# snes_exp_bridge.net
KiCad netlist of a schematic drawn in Altium Designer
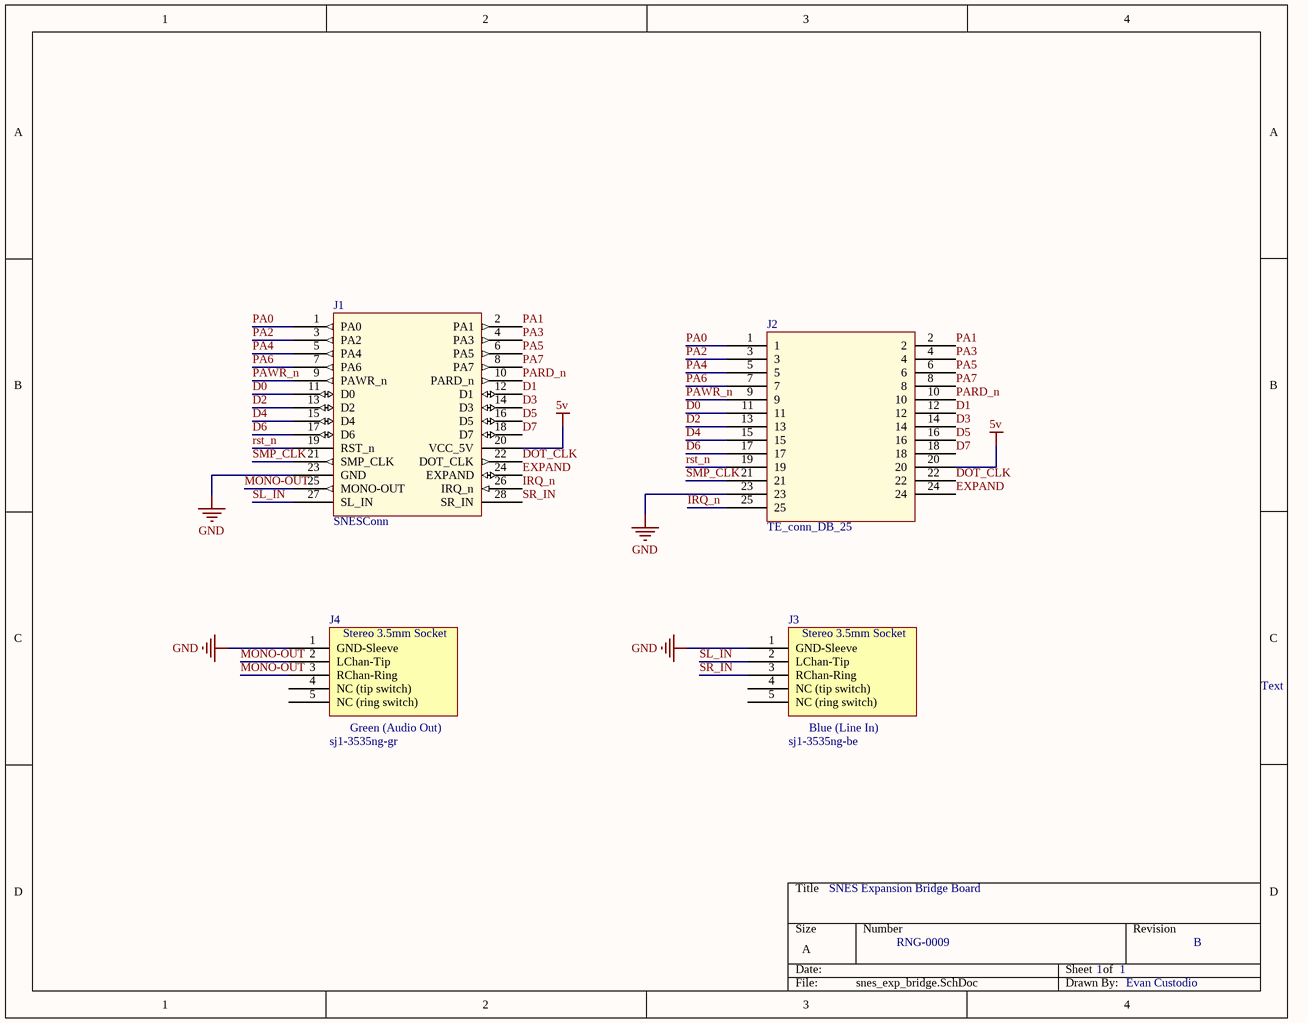
[diagram p0: snes_exp_bridge.SchDoc]

(export (version "E")
  (design (tool "Eeschema 10.0.6"))
  (components
    (comp (ref "J1")
      (value "SNESConn")
      (footprint "SNES-MEC2-CONN")
      (libsource (lib "snes_hook_parts") (part "SNESConn"))
    )
    (comp (ref "J2")
      (value "TE_conn_DB_25")
      (footprint "DB-25_RA_FSCK")
      (libsource (lib "snes_exp_bridge_parts") (part "TE_conn_DB_25"))
    )
    (comp (ref "J3")
      (value "sj1-3535ng-be")
      (footprint "SJ1-3535NG-BE")
      (libsource (lib "snes_exp_bridge_parts") (part "sj1-3535ng-be"))
    )
    (comp (ref "J4")
      (value "sj1-3535ng-gr")
      (footprint "SJ1-3535NG-GR")
      (libsource (lib "snes_exp_bridge_parts") (part "sj1-3535ng-gr"))
    )
  )
  (nets
    (net (code "1") (name "/D0") (class "Default")
      (node (ref "J1") (pin "11") (pinfunction "D0_11") (pintype "bidirectional"))
      (node (ref "J2") (pin "11") (pinfunction "11_11") (pintype "passive"))
    )
    (net (code "2") (name "/D1") (class "Default")
      (node (ref "J1") (pin "12") (pinfunction "D1_12") (pintype "bidirectional"))
      (node (ref "J2") (pin "12") (pinfunction "12_12") (pintype "passive"))
    )
    (net (code "3") (name "/D2") (class "Default")
      (node (ref "J1") (pin "13") (pinfunction "D2_13") (pintype "bidirectional"))
      (node (ref "J2") (pin "13") (pinfunction "13_13") (pintype "passive"))
    )
    (net (code "4") (name "/D3") (class "Default")
      (node (ref "J1") (pin "14") (pinfunction "D3_14") (pintype "bidirectional"))
      (node (ref "J2") (pin "14") (pinfunction "14_14") (pintype "passive"))
    )
    (net (code "5") (name "/D4") (class "Default")
      (node (ref "J1") (pin "15") (pinfunction "D4_15") (pintype "bidirectional"))
      (node (ref "J2") (pin "15") (pinfunction "15_15") (pintype "passive"))
    )
    (net (code "6") (name "/D5") (class "Default")
      (node (ref "J1") (pin "16") (pinfunction "D5_16") (pintype "bidirectional"))
      (node (ref "J2") (pin "16") (pinfunction "16_16") (pintype "passive"))
    )
    (net (code "7") (name "/D6") (class "Default")
      (node (ref "J1") (pin "17") (pinfunction "D6_17") (pintype "bidirectional"))
      (node (ref "J2") (pin "17") (pinfunction "17_17") (pintype "passive"))
    )
    (net (code "8") (name "/D7") (class "Default")
      (node (ref "J1") (pin "18") (pinfunction "D7_18") (pintype "bidirectional"))
      (node (ref "J2") (pin "18") (pinfunction "18_18") (pintype "passive"))
    )
    (net (code "9") (name "/DOT_CLK") (class "Default")
      (node (ref "J1") (pin "22") (pinfunction "DOT_CLK_22") (pintype "output"))
      (node (ref "J2") (pin "22") (pinfunction "22_22") (pintype "passive"))
    )
    (net (code "10") (name "/EXPAND") (class "Default")
      (node (ref "J1") (pin "24") (pinfunction "EXPAND_24") (pintype "bidirectional"))
      (node (ref "J2") (pin "24") (pinfunction "24_24") (pintype "passive"))
    )
    (net (code "11") (name "/IRQ_n") (class "Default")
      (node (ref "J1") (pin "26") (pinfunction "IRQ_n_26") (pintype "input"))
      (node (ref "J2") (pin "25") (pinfunction "25_25") (pintype "passive"))
    )
    (net (code "12") (name "/MONO-OUT") (class "Default")
      (node (ref "J1") (pin "25") (pinfunction "MONO-OUT_25") (pintype "output"))
      (node (ref "J4") (pin "2") (pinfunction "LChan-Tip_2") (pintype "passive"))
      (node (ref "J4") (pin "3") (pinfunction "RChan-Ring_3") (pintype "passive"))
    )
    (net (code "13") (name "/PA0") (class "Default")
      (node (ref "J1") (pin "1") (pinfunction "PA0_1") (pintype "output"))
      (node (ref "J2") (pin "1") (pinfunction "1_1") (pintype "passive"))
    )
    (net (code "14") (name "/PA1") (class "Default")
      (node (ref "J1") (pin "2") (pinfunction "PA1_2") (pintype "output"))
      (node (ref "J2") (pin "2") (pinfunction "2_2") (pintype "passive"))
    )
    (net (code "15") (name "/PA2") (class "Default")
      (node (ref "J1") (pin "3") (pinfunction "PA2_3") (pintype "output"))
      (node (ref "J2") (pin "3") (pinfunction "3_3") (pintype "passive"))
    )
    (net (code "16") (name "/PA3") (class "Default")
      (node (ref "J1") (pin "4") (pinfunction "PA3_4") (pintype "output"))
      (node (ref "J2") (pin "4") (pinfunction "4_4") (pintype "passive"))
    )
    (net (code "17") (name "/PA4") (class "Default")
      (node (ref "J1") (pin "5") (pinfunction "PA4_5") (pintype "output"))
      (node (ref "J2") (pin "5") (pinfunction "5_5") (pintype "passive"))
    )
    (net (code "18") (name "/PA5") (class "Default")
      (node (ref "J1") (pin "6") (pinfunction "PA5_6") (pintype "output"))
      (node (ref "J2") (pin "6") (pinfunction "6_6") (pintype "passive"))
    )
    (net (code "19") (name "/PA6") (class "Default")
      (node (ref "J1") (pin "7") (pinfunction "PA6_7") (pintype "output"))
      (node (ref "J2") (pin "7") (pinfunction "7_7") (pintype "passive"))
    )
    (net (code "20") (name "/PA7") (class "Default")
      (node (ref "J1") (pin "8") (pinfunction "PA7_8") (pintype "output"))
      (node (ref "J2") (pin "8") (pinfunction "8_8") (pintype "passive"))
    )
    (net (code "21") (name "/PARD_n") (class "Default")
      (node (ref "J1") (pin "10") (pinfunction "PARD_n_10") (pintype "output"))
      (node (ref "J2") (pin "10") (pinfunction "10_10") (pintype "passive"))
    )
    (net (code "22") (name "/PAWR_n") (class "Default")
      (node (ref "J1") (pin "9") (pinfunction "PAWR_n_9") (pintype "output"))
      (node (ref "J2") (pin "9") (pinfunction "9_9") (pintype "passive"))
    )
    (net (code "23") (name "/SL_IN") (class "Default")
      (node (ref "J1") (pin "27") (pinfunction "SL_IN_27") (pintype "passive"))
      (node (ref "J3") (pin "2") (pinfunction "LChan-Tip_2") (pintype "passive"))
    )
    (net (code "24") (name "/SMP_CLK") (class "Default")
      (node (ref "J1") (pin "21") (pinfunction "SMP_CLK_21") (pintype "output"))
      (node (ref "J2") (pin "21") (pinfunction "21_21") (pintype "passive"))
    )
    (net (code "25") (name "/SR_IN") (class "Default")
      (node (ref "J1") (pin "28") (pinfunction "SR_IN_28") (pintype "passive"))
      (node (ref "J3") (pin "3") (pinfunction "RChan-Ring_3") (pintype "passive"))
    )
    (net (code "26") (name "/rst_n") (class "Default")
      (node (ref "J1") (pin "19") (pinfunction "RST_n_19") (pintype "passive"))
      (node (ref "J2") (pin "19") (pinfunction "19_19") (pintype "passive"))
    )
    (net (code "27") (name "5v") (class "Default")
      (node (ref "J1") (pin "20") (pinfunction "VCC_5V_20") (pintype "passive"))
      (node (ref "J2") (pin "20") (pinfunction "20_20") (pintype "passive"))
    )
    (net (code "28") (name "GND") (class "Default")
      (node (ref "J1") (pin "23") (pinfunction "GND_23") (pintype "passive"))
      (node (ref "J2") (pin "23") (pinfunction "23_23") (pintype "passive"))
      (node (ref "J3") (pin "1") (pinfunction "GND-Sleeve_1") (pintype "passive"))
      (node (ref "J4") (pin "1") (pinfunction "GND-Sleeve_1") (pintype "passive"))
    )
    (net (code "29") (name "unconnected-(J3-NC_(ring_switch)-Pad5)") (class "Default")
      (node (ref "J3") (pin "5") (pinfunction "NC_(ring_switch)_5") (pintype "passive"))
    )
    (net (code "30") (name "unconnected-(J3-NC_(tip_switch)-Pad4)") (class "Default")
      (node (ref "J3") (pin "4") (pinfunction "NC_(tip_switch)_4") (pintype "passive"))
    )
    (net (code "31") (name "unconnected-(J4-NC_(ring_switch)-Pad5)") (class "Default")
      (node (ref "J4") (pin "5") (pinfunction "NC_(ring_switch)_5") (pintype "passive"))
    )
    (net (code "32") (name "unconnected-(J4-NC_(tip_switch)-Pad4)") (class "Default")
      (node (ref "J4") (pin "4") (pinfunction "NC_(tip_switch)_4") (pintype "passive"))
    )
  )
)
